# HB-OU-MP3-LED_V1_2.net
KiCad netlist of a schematic drawn in EAGLE
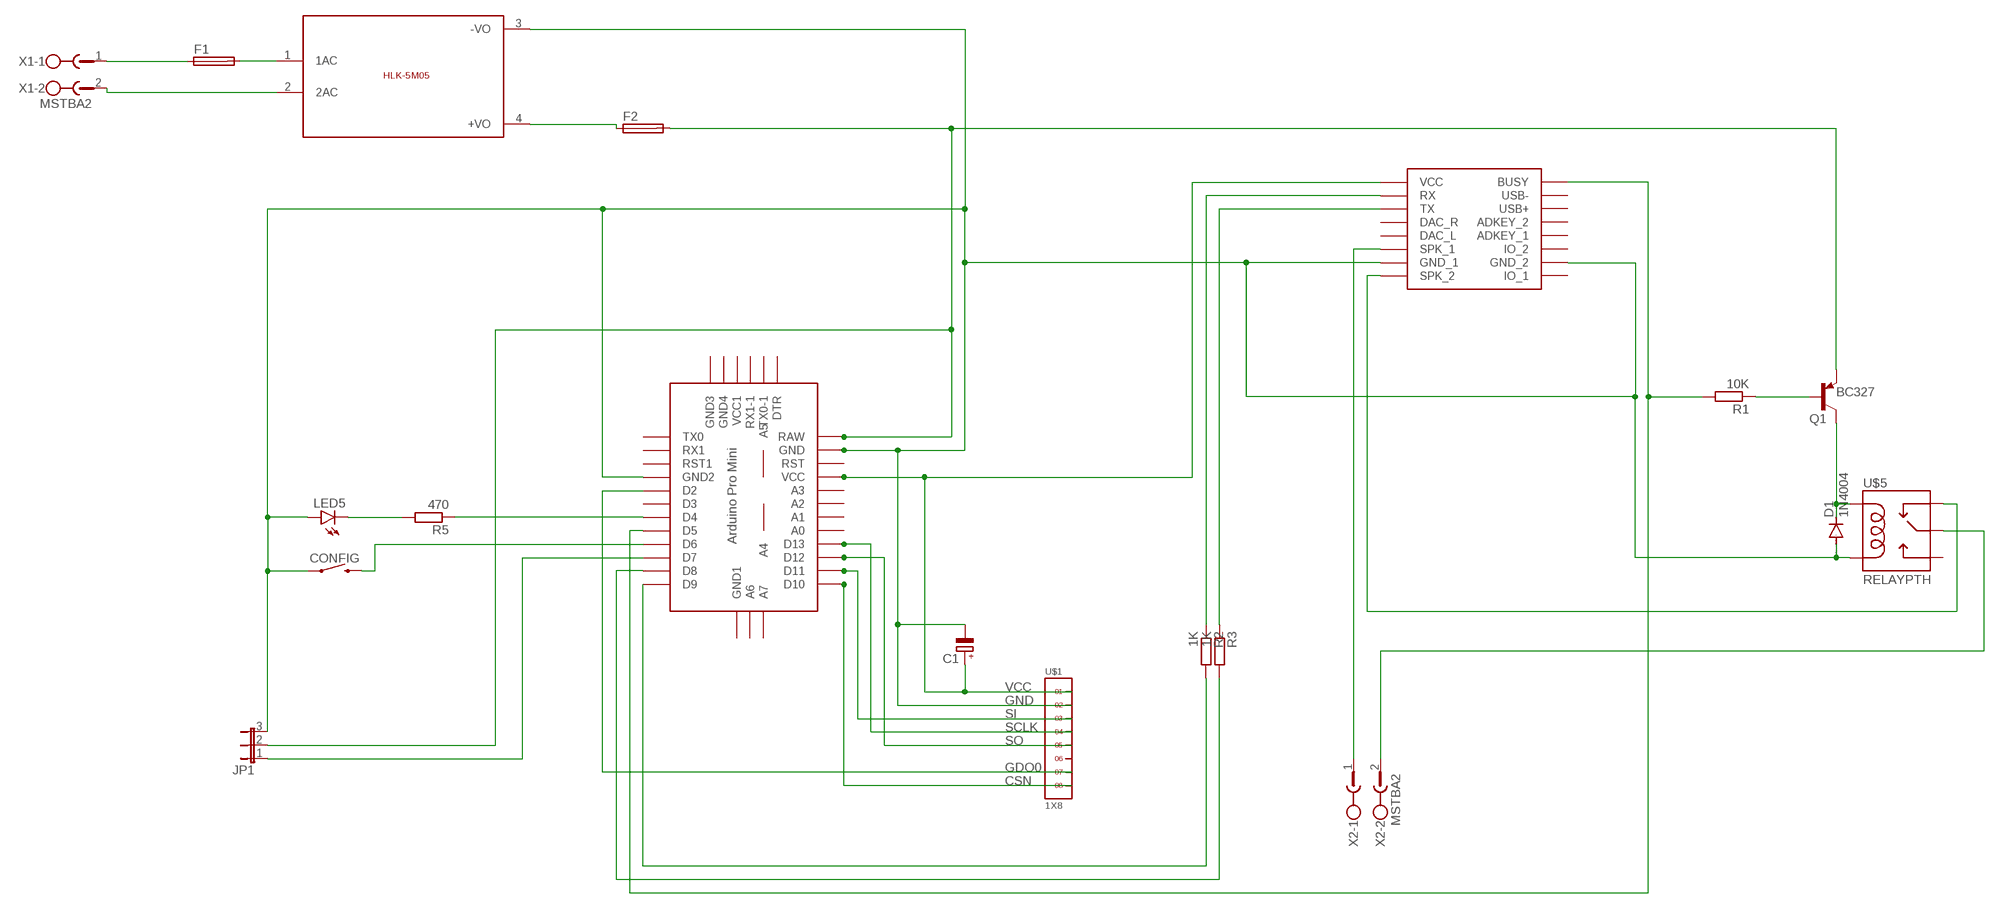
[diagram p0: schematic, sheet 1]

(export (version "E")
  (design (tool "Eeschema 10.0.6"))
  (components
    (comp (ref "C1")
      (value "CPOL-EUE2.5-5")
      (footprint "eagle-import:E2,5-5")
      (libsource (lib "eagle-import") (part "CPOL-EUE2.5-5"))
    )
    (comp (ref "CONFIG")
      (value "MOMENTARY-SWITCH-SPST-PTH-6.0MM-KIT")
      (footprint "eagle-import:TACTILE_SWITCH_PTH_6.0MM_KIT")
      (libsource (lib "eagle-import") (part "MOMENTARY-SWITCH-SPST-PTH-6.0MM-KIT"))
    )
    (comp (ref "D1")
      (value "1N4004")
      (footprint "eagle-import:DO41-10")
      (libsource (lib "eagle-import") (part "1N4004"))
    )
    (comp (ref "F1")
      (value "SH22,5A")
      (footprint "eagle-import:SH22,5A")
      (fields (field (name "MPN") "0031.7701.11"))
      (libsource (lib "eagle-import") (part "SH22,5A"))
    )
    (comp (ref "F2")
      (value "SH22,5A")
      (footprint "eagle-import:SH22,5A")
      (fields (field (name "MPN") "0031.7701.11"))
      (libsource (lib "eagle-import") (part "SH22,5A"))
    )
    (comp (ref "JP1")
      (value "JP2E")
      (footprint "eagle-import:JP2")
      (libsource (lib "eagle-import") (part "JP2E"))
    )
    (comp (ref "LED5")
      (value "LED3MM")
      (footprint "eagle-import:LED3MM")
      (libsource (lib "eagle-import") (part "LED3MM"))
    )
    (comp (ref "Q1")
      (value "BC327")
      (footprint "eagle-import:TO92")
      (libsource (lib "eagle-import") (part "BC327"))
    )
    (comp (ref "R1")
      (value "10K")
      (footprint "eagle-import:0309_10")
      (libsource (lib "eagle-import") (part "R-EU_0309/10"))
    )
    (comp (ref "R2")
      (value "1K")
      (footprint "eagle-import:0309_10")
      (libsource (lib "eagle-import") (part "R-EU_0309/10"))
    )
    (comp (ref "R3")
      (value "1K")
      (footprint "eagle-import:0309_10")
      (libsource (lib "eagle-import") (part "R-EU_0309/10"))
    )
    (comp (ref "R5")
      (value "470")
      (footprint "eagle-import:0309_10")
      (libsource (lib "eagle-import") (part "R-EU_0309/10"))
    )
    (comp (ref "U$1")
      (value "1X8")
      (footprint "eagle-import:1X8")
      (libsource (lib "eagle-import") (part "1X8"))
    )
    (comp (ref "U$2")
      (value "ABK-PRO-MINI")
      (footprint "eagle-import:ABK-PRO-MINI")
      (libsource (lib "eagle-import") (part "ABK-PRO-MINI"))
    )
    (comp (ref "U$3")
      (value "5VDC/5W")
      (footprint "eagle-import:HLK-5M05")
      (libsource (lib "eagle-import") (part "HLK-5M05"))
    )
    (comp (ref "U$4")
      (value "DFPLAYER")
      (footprint "eagle-import:DFPLAYER")
      (libsource (lib "eagle-import") (part "DFPLAYER"))
    )
    (comp (ref "U$5")
      (value "RELAYPTH")
      (footprint "eagle-import:SRD-05VDC-SL-C")
      (libsource (lib "eagle-import") (part "RELAYPTH"))
    )
    (comp (ref "X1")
      (value "MSTBA2")
      (footprint "eagle-import:MSTBA2")
      (fields (field (name "MF") "FARNELL") (field (name "MPN") "1757242"))
      (libsource (lib "eagle-import") (part "MSTBA2"))
    )
    (comp (ref "X2")
      (value "MSTBA2")
      (footprint "eagle-import:MSTBA2")
      (fields (field (name "MF") "FARNELL") (field (name "MPN") "1757242"))
      (libsource (lib "eagle-import") (part "MSTBA2"))
    )
  )
  (nets
    (net (code "1") (name "/CSN") (class "Default")
      (node (ref "U$1") (pin "8") (pinfunction "8_8") (pintype "bidirectional"))
      (node (ref "U$2") (pin "D10") (pinfunction "D10_D10") (pintype "bidirectional"))
    )
    (net (code "2") (name "/GDO0") (class "Default")
      (node (ref "U$1") (pin "7") (pinfunction "7_7") (pintype "bidirectional"))
      (node (ref "U$2") (pin "D2") (pinfunction "D2_D2") (pintype "bidirectional"))
    )
    (net (code "3") (name "/GND") (class "Default")
      (node (ref "C1") (pin "-") (pinfunction "-_-") (pintype "passive"))
      (node (ref "CONFIG") (pin "1") (pinfunction "1_1") (pintype "passive"))
      (node (ref "D1") (pin "A") (pinfunction "A_A") (pintype "passive"))
      (node (ref "JP1") (pin "3") (pinfunction "3_3") (pintype "passive"))
      (node (ref "LED5") (pin "A") (pinfunction "A_A") (pintype "passive"))
      (node (ref "U$1") (pin "2") (pinfunction "2_2") (pintype "bidirectional"))
      (node (ref "U$2") (pin "GND") (pinfunction "GND_GND") (pintype "bidirectional"))
      (node (ref "U$2") (pin "GND1") (pinfunction "GND2_GND1") (pintype "bidirectional"))
      (node (ref "U$3") (pin "3") (pinfunction "-VO_3") (pintype "bidirectional"))
      (node (ref "U$4") (pin "GND_1") (pinfunction "GND_1_GND_1") (pintype "bidirectional"))
      (node (ref "U$4") (pin "GND_2") (pinfunction "GND_2_GND_2") (pintype "bidirectional"))
      (node (ref "U$5") (pin "COIL0") (pinfunction "COIL0_COIL0") (pintype "bidirectional"))
    )
    (net (code "4") (name "/SCLK") (class "Default")
      (node (ref "U$1") (pin "4") (pinfunction "4_4") (pintype "bidirectional"))
      (node (ref "U$2") (pin "D13") (pinfunction "D13_D13") (pintype "bidirectional"))
    )
    (net (code "5") (name "/SI") (class "Default")
      (node (ref "U$1") (pin "3") (pinfunction "3_3") (pintype "bidirectional"))
      (node (ref "U$2") (pin "D11") (pinfunction "D11_D11") (pintype "bidirectional"))
    )
    (net (code "6") (name "/SO") (class "Default")
      (node (ref "U$1") (pin "5") (pinfunction "5_5") (pintype "bidirectional"))
      (node (ref "U$2") (pin "D12") (pinfunction "D12_D12") (pintype "bidirectional"))
    )
    (net (code "7") (name "/VCC") (class "Default")
      (node (ref "C1") (pin "+") (pinfunction "+_+") (pintype "passive"))
      (node (ref "U$1") (pin "1") (pinfunction "1_1") (pintype "bidirectional"))
      (node (ref "U$2") (pin "VCC") (pinfunction "VCC_VCC") (pintype "bidirectional"))
      (node (ref "U$4") (pin "VCC") (pinfunction "VCC_VCC") (pintype "bidirectional"))
    )
    (net (code "8") (name "Net-(CONFIG-2)") (class "Default")
      (node (ref "CONFIG") (pin "3") (pinfunction "2_3") (pintype "passive"))
      (node (ref "U$2") (pin "D6") (pinfunction "D6_D6") (pintype "bidirectional"))
    )
    (net (code "9") (name "Net-(F1-Pad1)") (class "Default")
      (node (ref "F1") (pin "1") (pinfunction "1_1") (pintype "passive"))
      (node (ref "X1") (pin "1") (pinfunction "1_1") (pintype "passive"))
    )
    (net (code "10") (name "Net-(JP1-Pad1)") (class "Default")
      (node (ref "JP1") (pin "1") (pinfunction "1_1") (pintype "passive"))
      (node (ref "U$2") (pin "D7") (pinfunction "D7_D7") (pintype "bidirectional"))
    )
    (net (code "11") (name "Net-(LED5-C)") (class "Default")
      (node (ref "LED5") (pin "K") (pinfunction "C_K") (pintype "passive"))
      (node (ref "R5") (pin "2") (pinfunction "2_2") (pintype "passive"))
    )
    (net (code "12") (name "Net-(Q1-B)") (class "Default")
      (node (ref "Q1") (pin "2") (pinfunction "B_2") (pintype "passive"))
      (node (ref "R1") (pin "1") (pinfunction "1_1") (pintype "passive"))
    )
    (net (code "13") (name "Net-(Q1-C)") (class "Default")
      (node (ref "D1") (pin "C") (pinfunction "C_C") (pintype "passive"))
      (node (ref "Q1") (pin "3") (pinfunction "C_3") (pintype "passive"))
      (node (ref "U$5") (pin "COIL1") (pinfunction "COIL1_COIL1") (pintype "bidirectional"))
    )
    (net (code "14") (name "Net-(Q1-E)") (class "Default")
      (node (ref "F2") (pin "2") (pinfunction "2_2") (pintype "passive"))
      (node (ref "JP1") (pin "2") (pinfunction "2_2") (pintype "passive"))
      (node (ref "Q1") (pin "1") (pinfunction "E_1") (pintype "passive"))
      (node (ref "U$2") (pin "RAW") (pinfunction "RAW_RAW") (pintype "bidirectional"))
    )
    (net (code "15") (name "Net-(R1-Pad2)") (class "Default")
      (node (ref "R1") (pin "2") (pinfunction "2_2") (pintype "passive"))
      (node (ref "U$2") (pin "D5") (pinfunction "D5_D5") (pintype "bidirectional"))
      (node (ref "U$4") (pin "BUSY") (pinfunction "BUSY_BUSY") (pintype "bidirectional"))
    )
    (net (code "16") (name "Net-(R2-Pad1)") (class "Default")
      (node (ref "R2") (pin "1") (pinfunction "1_1") (pintype "passive"))
      (node (ref "U$4") (pin "RX") (pinfunction "RX_RX") (pintype "bidirectional"))
    )
    (net (code "17") (name "Net-(R2-Pad2)") (class "Default")
      (node (ref "R2") (pin "2") (pinfunction "2_2") (pintype "passive"))
      (node (ref "U$2") (pin "D9") (pinfunction "D9_D9") (pintype "bidirectional"))
    )
    (net (code "18") (name "Net-(R3-Pad1)") (class "Default")
      (node (ref "R3") (pin "1") (pinfunction "1_1") (pintype "passive"))
      (node (ref "U$4") (pin "TX") (pinfunction "TX_TX") (pintype "bidirectional"))
    )
    (net (code "19") (name "Net-(R3-Pad2)") (class "Default")
      (node (ref "R3") (pin "2") (pinfunction "2_2") (pintype "passive"))
      (node (ref "U$2") (pin "D8") (pinfunction "D8_D8") (pintype "bidirectional"))
    )
    (net (code "20") (name "Net-(R5-Pad1)") (class "Default")
      (node (ref "R5") (pin "1") (pinfunction "1_1") (pintype "passive"))
      (node (ref "U$2") (pin "D4") (pinfunction "D4_D4") (pintype "bidirectional"))
    )
    (net (code "21") (name "Net-(U$3-+VO)") (class "Default")
      (node (ref "F2") (pin "1") (pinfunction "1_1") (pintype "passive"))
      (node (ref "U$3") (pin "4") (pinfunction "+VO_4") (pintype "bidirectional"))
    )
    (net (code "22") (name "Net-(U$3-1AC)") (class "Default")
      (node (ref "F1") (pin "2") (pinfunction "2_2") (pintype "passive"))
      (node (ref "U$3") (pin "1") (pinfunction "1AC_1") (pintype "bidirectional"))
    )
    (net (code "23") (name "Net-(U$3-2AC)") (class "Default")
      (node (ref "U$3") (pin "2") (pinfunction "2AC_2") (pintype "bidirectional"))
      (node (ref "X1") (pin "2") (pinfunction "1_2") (pintype "passive"))
    )
    (net (code "24") (name "Net-(U$4-SPK_1)") (class "Default")
      (node (ref "U$4") (pin "SPK1") (pinfunction "SPK_1_SPK1") (pintype "bidirectional"))
      (node (ref "X2") (pin "1") (pinfunction "1_1") (pintype "passive"))
    )
    (net (code "25") (name "Net-(U$4-SPK_2)") (class "Default")
      (node (ref "U$4") (pin "SPK2") (pinfunction "SPK_2_SPK2") (pintype "bidirectional"))
      (node (ref "U$5") (pin "SWCLOSED") (pinfunction "SWCLOSE_SWCLOSED") (pintype "bidirectional"))
    )
    (net (code "26") (name "Net-(X2B-1)") (class "Default")
      (node (ref "U$5") (pin "SWCOMMON") (pinfunction "SWCOMMON_SWCOMMON") (pintype "bidirectional"))
      (node (ref "X2") (pin "2") (pinfunction "1_2") (pintype "passive"))
    )
    (net (code "27") (name "unconnected-(U$1-Pad6)") (class "Default")
      (node (ref "U$1") (pin "6") (pinfunction "6_6") (pintype "bidirectional"))
    )
    (net (code "28") (name "unconnected-(U$2-GND1-PadGND4)") (class "Default")
      (node (ref "U$2") (pin "GND4") (pinfunction "GND1_GND4") (pintype "bidirectional"))
    )
    (net (code "29") (name "unconnected-(U$2-GND3-PadGND2)") (class "Default")
      (node (ref "U$2") (pin "GND2") (pinfunction "GND3_GND2") (pintype "bidirectional"))
    )
    (net (code "30") (name "unconnected-(U$2-GND4-PadGND3)") (class "Default")
      (node (ref "U$2") (pin "GND3") (pinfunction "GND4_GND3") (pintype "bidirectional"))
    )
    (net (code "31") (name "unconnected-(U$2-PadA0)") (class "Default")
      (node (ref "U$2") (pin "A0") (pinfunction "A0_A0") (pintype "bidirectional"))
    )
    (net (code "32") (name "unconnected-(U$2-PadA1)") (class "Default")
      (node (ref "U$2") (pin "A1") (pinfunction "A1_A1") (pintype "bidirectional"))
    )
    (net (code "33") (name "unconnected-(U$2-PadA2)") (class "Default")
      (node (ref "U$2") (pin "A2") (pinfunction "A2_A2") (pintype "bidirectional"))
    )
    (net (code "34") (name "unconnected-(U$2-PadA3)") (class "Default")
      (node (ref "U$2") (pin "A3") (pinfunction "A3_A3") (pintype "bidirectional"))
    )
    (net (code "35") (name "unconnected-(U$2-PadA4)") (class "Default")
      (node (ref "U$2") (pin "A4") (pinfunction "A4_A4") (pintype "bidirectional"))
    )
    (net (code "36") (name "unconnected-(U$2-PadA5)") (class "Default")
      (node (ref "U$2") (pin "A5") (pinfunction "A5_A5") (pintype "bidirectional"))
    )
    (net (code "37") (name "unconnected-(U$2-PadA6)") (class "Default")
      (node (ref "U$2") (pin "A6") (pinfunction "A6_A6") (pintype "bidirectional"))
    )
    (net (code "38") (name "unconnected-(U$2-PadA7)") (class "Default")
      (node (ref "U$2") (pin "A7") (pinfunction "A7_A7") (pintype "bidirectional"))
    )
    (net (code "39") (name "unconnected-(U$2-PadD3)") (class "Default")
      (node (ref "U$2") (pin "D3") (pinfunction "D3_D3") (pintype "bidirectional"))
    )
    (net (code "40") (name "unconnected-(U$2-PadDTR)") (class "Default")
      (node (ref "U$2") (pin "DTR") (pinfunction "DTR_DTR") (pintype "bidirectional"))
    )
    (net (code "41") (name "unconnected-(U$2-PadRST)") (class "Default")
      (node (ref "U$2") (pin "RST") (pinfunction "RST_RST") (pintype "bidirectional"))
    )
    (net (code "42") (name "unconnected-(U$2-PadRST1)") (class "Default")
      (node (ref "U$2") (pin "RST1") (pinfunction "RST1_RST1") (pintype "bidirectional"))
    )
    (net (code "43") (name "unconnected-(U$2-PadRX1)") (class "Default")
      (node (ref "U$2") (pin "RX1") (pinfunction "RX1_RX1") (pintype "bidirectional"))
    )
    (net (code "44") (name "unconnected-(U$2-PadRX1-1)") (class "Default")
      (node (ref "U$2") (pin "RX1-1") (pinfunction "RX1-1_RX1-1") (pintype "bidirectional"))
    )
    (net (code "45") (name "unconnected-(U$2-PadTX0)") (class "Default")
      (node (ref "U$2") (pin "TX0") (pinfunction "TX0_TX0") (pintype "bidirectional"))
    )
    (net (code "46") (name "unconnected-(U$2-PadTX0-1)") (class "Default")
      (node (ref "U$2") (pin "TX0-1") (pinfunction "TX0-1_TX0-1") (pintype "bidirectional"))
    )
    (net (code "47") (name "unconnected-(U$2-PadVCC1)") (class "Default")
      (node (ref "U$2") (pin "VCC1") (pinfunction "VCC1_VCC1") (pintype "bidirectional"))
    )
    (net (code "48") (name "unconnected-(U$4-ADKEY_1-PadADKEY1)") (class "Default")
      (node (ref "U$4") (pin "ADKEY1") (pinfunction "ADKEY_1_ADKEY1") (pintype "bidirectional"))
    )
    (net (code "49") (name "unconnected-(U$4-ADKEY_2-PadADKEY2)") (class "Default")
      (node (ref "U$4") (pin "ADKEY2") (pinfunction "ADKEY_2_ADKEY2") (pintype "bidirectional"))
    )
    (net (code "50") (name "unconnected-(U$4-IO_1-PadIO1)") (class "Default")
      (node (ref "U$4") (pin "IO1") (pinfunction "IO_1_IO1") (pintype "bidirectional"))
    )
    (net (code "51") (name "unconnected-(U$4-IO_2-PadIO2)") (class "Default")
      (node (ref "U$4") (pin "IO2") (pinfunction "IO_2_IO2") (pintype "bidirectional"))
    )
    (net (code "52") (name "unconnected-(U$4-PadDAC_L)") (class "Default")
      (node (ref "U$4") (pin "DAC_L") (pinfunction "DAC_L_DAC_L") (pintype "bidirectional"))
    )
    (net (code "53") (name "unconnected-(U$4-PadDAC_R)") (class "Default")
      (node (ref "U$4") (pin "DAC_R") (pinfunction "DAC_R_DAC_R") (pintype "bidirectional"))
    )
    (net (code "54") (name "unconnected-(U$4-PadUSB+)") (class "Default")
      (node (ref "U$4") (pin "USB+") (pinfunction "USB+_USB+") (pintype "bidirectional"))
    )
    (net (code "55") (name "unconnected-(U$4-PadUSB-)") (class "Default")
      (node (ref "U$4") (pin "USB-") (pinfunction "USB-_USB-") (pintype "bidirectional"))
    )
    (net (code "56") (name "unconnected-(U$5-PadSWOPEN)") (class "Default")
      (node (ref "U$5") (pin "SWOPEN") (pinfunction "SWOPEN_SWOPEN") (pintype "bidirectional"))
    )
  )
)
